# relay_w_diodes.net
KiCad netlist of a schematic drawn in EAGLE
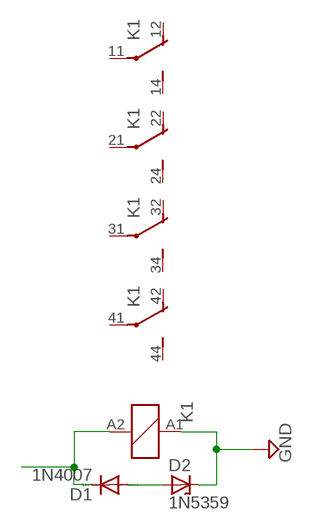
[diagram p0: schematic, sheet 1]

(export (version "E")
  (design (tool "Eeschema 10.0.6"))
  (components
    (comp (ref "D1")
      (value "1N4007")
      (footprint "eagle-import:DO41-10")
      (libsource (lib "eagle-import") (part "1N4007"))
    )
    (comp (ref "D2")
      (value "1N5359")
      (footprint "eagle-import:C1702-15")
      (libsource (lib "eagle-import") (part "1N5359"))
    )
    (comp (ref "K1")
      (value "PY14-02")
      (footprint "eagle-import:PY14-02")
      (libsource (lib "eagle-import") (part "PY14-02"))
    )
  )
  (nets
    (net (code "1") (name "GND") (class "Default")
      (node (ref "D2") (pin "C") (pinfunction "C_C") (pintype "passive"))
      (node (ref "K1") (pin "A1") (pinfunction "1_A1") (pintype "passive"))
    )
    (net (code "2") (name "Net-(D1-PadA)") (class "Default")
      (node (ref "D1") (pin "A") (pinfunction "A_A") (pintype "passive"))
      (node (ref "D2") (pin "A") (pinfunction "A_A") (pintype "passive"))
    )
    (net (code "3") (name "Net-(K1A-2)") (class "Default")
      (node (ref "D1") (pin "C") (pinfunction "C_C") (pintype "passive"))
      (node (ref "K1") (pin "A2") (pinfunction "2_A2") (pintype "passive"))
    )
    (net (code "4") (name "unconnected-(K1B-O-Pad12)") (class "Default")
      (node (ref "K1") (pin "12") (pinfunction "O_12") (pintype "passive"))
    )
    (net (code "5") (name "unconnected-(K1B-P-Pad11)") (class "Default")
      (node (ref "K1") (pin "11") (pinfunction "P_11") (pintype "passive"))
    )
    (net (code "6") (name "unconnected-(K1B-S-Pad14)") (class "Default")
      (node (ref "K1") (pin "14") (pinfunction "S_14") (pintype "passive"))
    )
    (net (code "7") (name "unconnected-(K1C-O-Pad22)") (class "Default")
      (node (ref "K1") (pin "22") (pinfunction "O_22") (pintype "passive"))
    )
    (net (code "8") (name "unconnected-(K1C-P-Pad21)") (class "Default")
      (node (ref "K1") (pin "21") (pinfunction "P_21") (pintype "passive"))
    )
    (net (code "9") (name "unconnected-(K1C-S-Pad24)") (class "Default")
      (node (ref "K1") (pin "24") (pinfunction "S_24") (pintype "passive"))
    )
    (net (code "10") (name "unconnected-(K1D-O-Pad32)") (class "Default")
      (node (ref "K1") (pin "32") (pinfunction "O_32") (pintype "passive"))
    )
    (net (code "11") (name "unconnected-(K1D-P-Pad31)") (class "Default")
      (node (ref "K1") (pin "31") (pinfunction "P_31") (pintype "passive"))
    )
    (net (code "12") (name "unconnected-(K1D-S-Pad34)") (class "Default")
      (node (ref "K1") (pin "34") (pinfunction "S_34") (pintype "passive"))
    )
    (net (code "13") (name "unconnected-(K1E-O-Pad42)") (class "Default")
      (node (ref "K1") (pin "42") (pinfunction "O_42") (pintype "passive"))
    )
    (net (code "14") (name "unconnected-(K1E-P-Pad41)") (class "Default")
      (node (ref "K1") (pin "41") (pinfunction "P_41") (pintype "passive"))
    )
    (net (code "15") (name "unconnected-(K1E-S-Pad44)") (class "Default")
      (node (ref "K1") (pin "44") (pinfunction "S_44") (pintype "passive"))
    )
  )
)
